# CHARGER_2A.net
KiCad netlist of a schematic drawn in Altium Designer
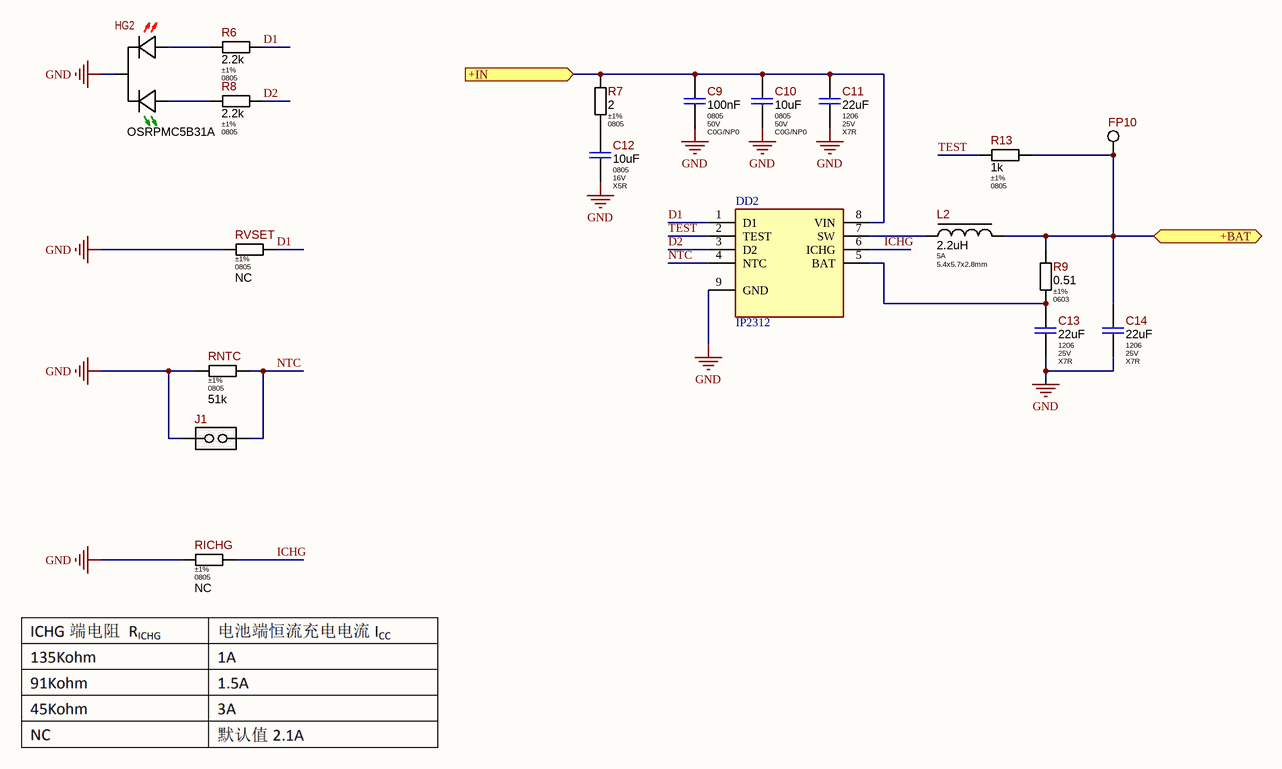
[diagram p0: CHARGER_2A.SchDoc]

(export (version "E")
  (design (tool "Eeschema 10.0.6"))
  (components
    (comp (ref "C9")
      (value "100nF")
      (footprint "C_CERAMIC_0805_HI")
      (fields
        (field (name "PART NUMBER") "**")
        (field (name "MANUFACTURER") "Hitano")
        (field (name "TOLERANCE") "±5%")
        (field (name "PACKAGE") "0805")
        (field (name "VOLTAGE") "50V")
        (field (name "DIELECTRIC TYPE") "C0G/NP0")
      )
      (libsource (lib "vitech_capacitors") (part "CERAMIC_0805"))
    )
    (comp (ref "C10")
      (value "10uF")
      (footprint "C_CERAMIC_0805_HI")
      (fields
        (field (name "PART NUMBER") "**")
        (field (name "MANUFACTURER") "Hitano")
        (field (name "TOLERANCE") "±5%")
        (field (name "PACKAGE") "0805")
        (field (name "VOLTAGE") "50V")
        (field (name "DIELECTRIC TYPE") "C0G/NP0")
      )
      (libsource (lib "vitech_capacitors") (part "CERAMIC_0805"))
    )
    (comp (ref "C11")
      (value "22uF")
      (footprint "C_CERAMIC_1206_MED")
      (description "22uF 25V")
      (fields
        (field (name "PACKAGE") "1206")
        (field (name "VOLTAGE") "25V")
        (field (name "DIELECTRIC TYPE") "X7R")
        (field (name "PART NUMBER") "CL31A226KAHNNNE")
        (field (name "MANUFACTURER") "SAMSUNG")
      )
      (libsource (lib "vitech_capacitors") (part "1206B102K102CG"))
    )
    (comp (ref "C12")
      (value "10uF")
      (footprint "CAP-0805(2012)X125T15")
      (description "10uF 16V Х5R ±10% 0805 Ceramic Capacitor RoHS")
      (fields
        (field (name "PACKAGE") "0805")
        (field (name "VOLTAGE") "16V")
        (field (name "DIELECTRIC TYPE") "X5R")
        (field (name "PART NUMBER") "CL21A106KOQNNNE")
        (field (name "MANUFACTURER") "Samsung Electro-Mechanics")
      )
      (libsource (lib "capacitors") (part "CL21A106KOQNNNE"))
    )
    (comp (ref "C13")
      (value "22uF")
      (footprint "C_CERAMIC_1206_MED")
      (description "22uF 25V")
      (fields
        (field (name "PACKAGE") "1206")
        (field (name "VOLTAGE") "25V")
        (field (name "DIELECTRIC TYPE") "X7R")
        (field (name "PART NUMBER") "CL31A226KAHNNNE")
        (field (name "MANUFACTURER") "SAMSUNG")
      )
      (libsource (lib "vitech_capacitors") (part "1206B102K102CG"))
    )
    (comp (ref "C14")
      (value "22uF")
      (footprint "C_CERAMIC_1206_MED")
      (description "22uF 25V")
      (fields
        (field (name "PACKAGE") "1206")
        (field (name "VOLTAGE") "25V")
        (field (name "DIELECTRIC TYPE") "X7R")
        (field (name "PART NUMBER") "CL31A226KAHNNNE")
        (field (name "MANUFACTURER") "SAMSUNG")
      )
      (libsource (lib "vitech_capacitors") (part "1206B102K102CG"))
    )
    (comp (ref "DD2") (value "IP2312") (footprint "IP2313") (libsource (lib "vitech_lib") (part "IP2312")))
    (comp (ref "FP10")
      (value "PAD-1.45mm")
      (footprint "PAD-1.45mm")
      (description "1.45mm Pad for Plug-In or Receptacle")
      (fields (field (name "MANUFACTURER") "NONE"))
      (libsource (lib "probetools") (part "PAD-1.45mm"))
    )
    (comp (ref "HG2")
      (value "OSRPMC5B31A")
      (footprint "OSRPMC5B31A")
      (description "5mm Phoenix Red & Pure Green LED, 625nm and 525nm, 30°")
      (fields (field (name "PART NUMBER") "OSRPMC5B31A") (field (name "MANUFACTURER") "OptoSupply"))
      (libsource (lib "opto") (part "OSRPMC5B31A"))
    )
    (comp (ref "J1")
      (value "PLS-2 (Part of PLS-40)")
      (footprint "PLS-2")
      (description "2 Pin 2.54mm Male Header, Vertical, 3mm and 6.1mm, PLS-2")
      (fields (field (name "PART NUMBER") "DS1021-02SF11") (field (name "MANUFACTURER") "Connfly"))
      (libsource (lib "connectors") (part "DS1021-02SF11"))
    )
    (comp (ref "L2")
      (value "2.2uH")
      (footprint "BMRA00050530-Series")
      (description "2.2uH 5A 35mOhm max Closed Magnetic, Molding Processing, Ultra High Current Power Inductor")
      (fields
        (field (name "CURRENT") "5A")
        (field (name "PACKAGE") "5.4x5.7x2.8mm")
        (field (name "PART NUMBER") "BMRA000505302R2MA1")
        (field (name "TOLERANCE") "±20%")
      )
      (libsource (lib "inductors") (part "BMRA000505302R2MA1"))
    )
    (comp (ref "R6")
      (value "2.2k")
      (footprint "R_ANY_CHIP_0805_MED")
      (description "2.2 kOhms ±1% 1/8W 0805 Thick Film Resistor")
      (fields
        (field (name "TOLERANCE") "±1%")
        (field (name "PACKAGE") "0805")
        (field (name "PART NUMBER") "RC0805FR-072K2L")
        (field (name "MANUFACTURER") "Yageo")
      )
      (libsource (lib "resistors") (part "RC0805FR-072K2L"))
    )
    (comp (ref "R7")
      (value "2")
      (footprint "R_ANY_CHIP_0805_MED")
      (description "2 Ohm ±1%, 1/8W 0805 Thick Film Resistor")
      (fields
        (field (name "TOLERANCE") "±1%")
        (field (name "PACKAGE") "0805")
        (field (name "PART NUMBER") "RC0805FR-072RL")
        (field (name "MANUFACTURER") "Yageo")
      )
      (libsource (lib "resistors") (part "RC0805FR-072RL"))
    )
    (comp (ref "R8")
      (value "2.2k")
      (footprint "R_ANY_CHIP_0805_MED")
      (description "2.2 kOhms ±1% 1/8W 0805 Thick Film Resistor")
      (fields
        (field (name "TOLERANCE") "±1%")
        (field (name "PACKAGE") "0805")
        (field (name "PART NUMBER") "RC0805FR-072K2L")
        (field (name "MANUFACTURER") "Yageo")
      )
      (libsource (lib "resistors") (part "RC0805FR-072K2L"))
    )
    (comp (ref "R9")
      (value "0.51")
      (footprint "R_ANY_CHIP_0603_MED")
      (description "510 mOhms ±1%, 1/10W 0603 Thick Film Resistor")
      (fields
        (field (name "TOLERANCE") "±1%")
        (field (name "PACKAGE") "0603")
        (field (name "PART NUMBER") "RL0603FR-070R51L")
        (field (name "MANUFACTURER") "Yageo")
      )
      (libsource (lib "resistors") (part "RL0603FR-070R51L"))
    )
    (comp (ref "R13")
      (value "1k")
      (footprint "R_ANY_CHIP_0805_MED")
      (description "1 kOhms ±1%, 1/8W 0805 Thick Film Resistor")
      (fields
        (field (name "TOLERANCE") "±1%")
        (field (name "PACKAGE") "0805")
        (field (name "PART NUMBER") "RC0805FR-071KL")
        (field (name "MANUFACTURER") "Yageo")
      )
      (libsource (lib "resistors") (part "RC0805FR-071KL"))
    )
    (comp (ref "RICHG")
      (value "NC")
      (footprint "R_ANY_CHIP_0805_MED")
      (fields
        (field (name "TOLERANCE") "±1%")
        (field (name "PACKAGE") "0805")
        (field (name "PART NUMBER") "RC0805FR-07120RL")
        (field (name "MANUFACTURER") "Yageo")
        (field (name "VOLTAGE") "150V")
      )
      (libsource (lib "resistors") (part "RC0805FR-07120RL"))
    )
    (comp (ref "RNTC")
      (value "51k")
      (footprint "R_ANY_CHIP_0805_MED")
      (fields
        (field (name "TOLERANCE") "±1%")
        (field (name "PACKAGE") "0805")
        (field (name "PART NUMBER") "0805S8F5102T5E")
        (field (name "MANUFACTURER") "Yageo")
        (field (name "VOLTAGE") "150V")
      )
      (libsource (lib "resistors") (part "RC0805FR-07120RL"))
    )
    (comp (ref "RVSET")
      (value "NC")
      (footprint "R_ANY_CHIP_0805_MED")
      (fields
        (field (name "TOLERANCE") "±1%")
        (field (name "PACKAGE") "0805")
        (field (name "PART NUMBER") "RC0805FR-07120RL")
        (field (name "MANUFACTURER") "Yageo")
        (field (name "VOLTAGE") "150V")
      )
      (libsource (lib "resistors") (part "RC0805FR-07120RL"))
    )
  )
  (nets
    (net (code "1") (name "/+BAT") (class "Default")
      (node (ref "C14") (pin "1") (pinfunction "1_1") (pintype "passive"))
      (node (ref "FP10") (pin "1") (pintype "passive"))
      (node (ref "L2") (pin "2") (pintype "passive"))
      (node (ref "R13") (pin "2") (pintype "passive"))
      (node (ref "R9") (pin "1") (pintype "passive"))
    )
    (net (code "2") (name "/+IN") (class "Default")
      (node (ref "C10") (pin "1") (pinfunction "1_1") (pintype "passive"))
      (node (ref "C11") (pin "1") (pinfunction "1_1") (pintype "passive"))
      (node (ref "C9") (pin "1") (pinfunction "1_1") (pintype "passive"))
      (node (ref "DD2") (pin "8") (pinfunction "VIN_8") (pintype "passive"))
      (node (ref "R7") (pin "1") (pintype "passive"))
    )
    (net (code "3") (name "/D1") (class "Default")
      (node (ref "DD2") (pin "1") (pinfunction "D1_1") (pintype "passive"))
      (node (ref "R6") (pin "2") (pintype "passive"))
      (node (ref "RVSET") (pin "2") (pintype "passive"))
    )
    (net (code "4") (name "/D2") (class "Default")
      (node (ref "DD2") (pin "3") (pinfunction "D2_3") (pintype "passive"))
      (node (ref "R8") (pin "2") (pintype "passive"))
    )
    (net (code "5") (name "/ICHG") (class "Default")
      (node (ref "DD2") (pin "6") (pinfunction "ICHG_6") (pintype "passive"))
      (node (ref "RICHG") (pin "2") (pintype "passive"))
    )
    (net (code "6") (name "/NTC") (class "Default")
      (node (ref "DD2") (pin "4") (pinfunction "NTC_4") (pintype "passive"))
      (node (ref "J1") (pin "2") (pintype "passive"))
      (node (ref "RNTC") (pin "2") (pintype "passive"))
    )
    (net (code "7") (name "/TEST") (class "Default")
      (node (ref "DD2") (pin "2") (pinfunction "TEST_2") (pintype "passive"))
      (node (ref "R13") (pin "1") (pintype "passive"))
    )
    (net (code "8") (name "GND") (class "Default")
      (node (ref "C10") (pin "2") (pinfunction "2_2") (pintype "passive"))
      (node (ref "C11") (pin "2") (pinfunction "2_2") (pintype "passive"))
      (node (ref "C12") (pin "2") (pinfunction "2_2") (pintype "passive"))
      (node (ref "C13") (pin "2") (pinfunction "2_2") (pintype "passive"))
      (node (ref "C14") (pin "2") (pinfunction "2_2") (pintype "passive"))
      (node (ref "C9") (pin "2") (pinfunction "2_2") (pintype "passive"))
      (node (ref "DD2") (pin "9") (pinfunction "GND_9") (pintype "passive"))
      (node (ref "HG2") (pin "CC") (pinfunction "Cathode_CC") (pintype "passive"))
      (node (ref "J1") (pin "1") (pintype "passive"))
      (node (ref "RICHG") (pin "1") (pintype "passive"))
      (node (ref "RNTC") (pin "1") (pintype "passive"))
      (node (ref "RVSET") (pin "1") (pintype "passive"))
    )
    (net (code "9") (name "Net-(C12-Pad1)") (class "Default")
      (node (ref "C12") (pin "1") (pinfunction "1_1") (pintype "passive"))
      (node (ref "R7") (pin "2") (pintype "passive"))
    )
    (net (code "10") (name "Net-(DD2-BAT)") (class "Default")
      (node (ref "C13") (pin "1") (pinfunction "1_1") (pintype "passive"))
      (node (ref "DD2") (pin "5") (pinfunction "BAT_5") (pintype "passive"))
      (node (ref "R9") (pin "2") (pintype "passive"))
    )
    (net (code "11") (name "Net-(DD2-SW)") (class "Default")
      (node (ref "DD2") (pin "7") (pinfunction "SW_7") (pintype "passive"))
      (node (ref "L2") (pin "1") (pintype "passive"))
    )
    (net (code "12") (name "Net-(HG2-PadA1)") (class "Default")
      (node (ref "HG2") (pin "A1") (pintype "passive"))
      (node (ref "R6") (pin "1") (pintype "passive"))
    )
    (net (code "13") (name "Net-(HG2-PadA2)") (class "Default")
      (node (ref "HG2") (pin "A2") (pintype "passive"))
      (node (ref "R8") (pin "1") (pintype "passive"))
    )
  )
)
